# Clock_Schematic_v_7.net
KiCad netlist of a schematic drawn in EAGLE
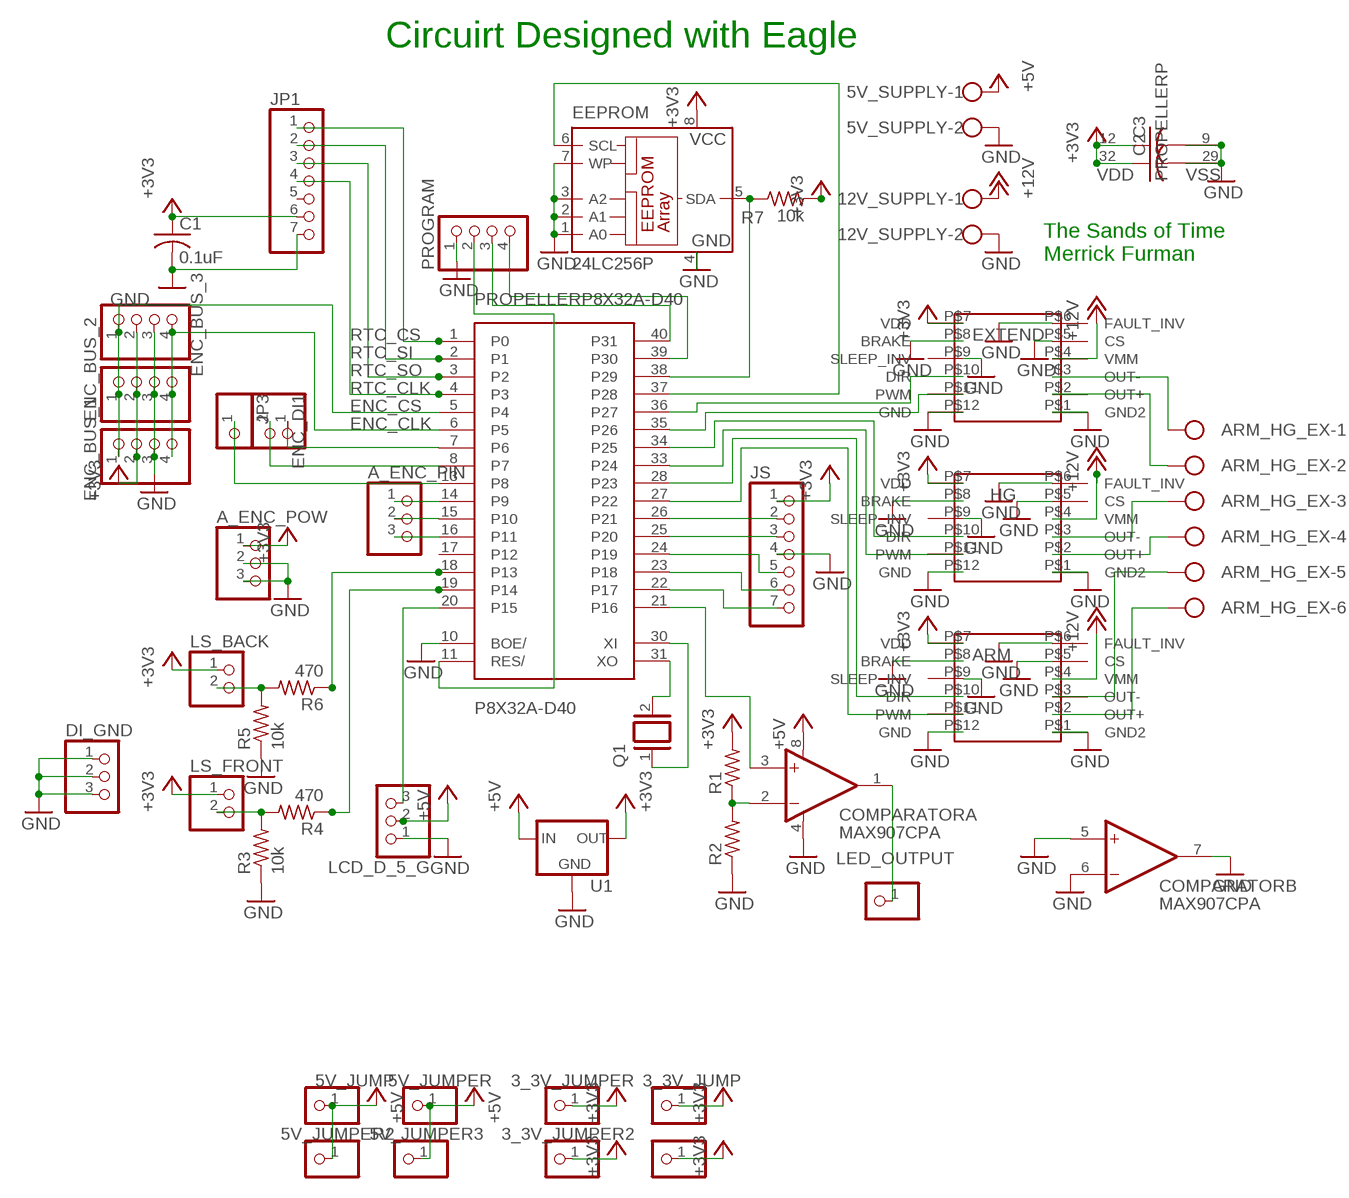
[diagram p0: schematic, sheet 1]

(export (version "E")
  (design (tool "Eeschema 10.0.6"))
  (components
    (comp (ref "3_3V_JUMP")
      (value "PINHD-1X1")
      (footprint "eagle-import:1X01")
      (libsource (lib "eagle-import") (part "PINHD-1X1"))
    )
    (comp (ref "3_3V_JUMPER")
      (value "PINHD-1X1")
      (footprint "eagle-import:1X01")
      (libsource (lib "eagle-import") (part "PINHD-1X1"))
    )
    (comp (ref "3_3V_JUMPER2")
      (value "PINHD-1X1")
      (footprint "eagle-import:1X01")
      (libsource (lib "eagle-import") (part "PINHD-1X1"))
    )
    (comp (ref "3_3V_JUMPER3")
      (value "PINHD-1X1")
      (footprint "eagle-import:1X01")
      (libsource (lib "eagle-import") (part "PINHD-1X1"))
    )
    (comp (ref "5V_JUMP")
      (value "PINHD-1X1")
      (footprint "eagle-import:1X01")
      (libsource (lib "eagle-import") (part "PINHD-1X1"))
    )
    (comp (ref "5V_JUMPER")
      (value "PINHD-1X1")
      (footprint "eagle-import:1X01")
      (libsource (lib "eagle-import") (part "PINHD-1X1"))
    )
    (comp (ref "5V_JUMPER2")
      (value "PINHD-1X1")
      (footprint "eagle-import:1X01")
      (libsource (lib "eagle-import") (part "PINHD-1X1"))
    )
    (comp (ref "5V_JUMPER3")
      (value "PINHD-1X1")
      (footprint "eagle-import:1X01")
      (libsource (lib "eagle-import") (part "PINHD-1X1"))
    )
    (comp (ref "5V_SUPPLY")
      (value "W237-102")
      (footprint "eagle-import:W237-102")
      (fields (field (name "MPN") "237-102"))
      (libsource (lib "eagle-import") (part "W237-102"))
    )
    (comp (ref "12V_SUPPLY")
      (value "W237-102")
      (footprint "eagle-import:W237-102")
      (fields (field (name "MPN") "237-102"))
      (libsource (lib "eagle-import") (part "W237-102"))
    )
    (comp (ref "ARM")
      (value "DRV")
      (footprint "eagle-import:DRV")
      (libsource (lib "eagle-import") (part "DRV"))
    )
    (comp (ref "ARM_HG_EX")
      (value "W237-6")
      (footprint "eagle-import:W237-6")
      (libsource (lib "eagle-import") (part "W237-6"))
    )
    (comp (ref "A_ENC_PIN")
      (value "PINHD-1X3")
      (footprint "eagle-import:1X03")
      (libsource (lib "eagle-import") (part "PINHD-1X3"))
    )
    (comp (ref "A_ENC_POW")
      (value "PINHD-1X3")
      (footprint "eagle-import:1X03")
      (libsource (lib "eagle-import") (part "PINHD-1X3"))
    )
    (comp (ref "C1")
      (value "0.1uF")
      (footprint "eagle-import:C050-025X075")
      (libsource (lib "eagle-import") (part "C-US050-025X075"))
    )
    (comp (ref "C2")
      (value "C-US050-025X075")
      (footprint "eagle-import:C050-025X075")
      (libsource (lib "eagle-import") (part "C-US050-025X075"))
    )
    (comp (ref "C3")
      (value "C-US050-025X075")
      (footprint "eagle-import:C050-025X075")
      (libsource (lib "eagle-import") (part "C-US050-025X075"))
    )
    (comp (ref "COMPARATOR")
      (value "MAX907CPA")
      (footprint "eagle-import:DIL08")
      (fields (field (name "MF") "MAXIM") (field (name "SPICEPREFIX") "X"))
      (libsource (lib "eagle-import") (part "MAX907CPA"))
    )
    (comp (ref "DI_GND")
      (value "PINHD-1X3")
      (footprint "eagle-import:1X03")
      (libsource (lib "eagle-import") (part "PINHD-1X3"))
    )
    (comp (ref "EEPROM")
      (value "24LC256P")
      (footprint "eagle-import:DIL8")
      (fields (field (name "MF") "MICROCHIP") (field (name "MPN") "24LC256-E/P"))
      (libsource (lib "eagle-import") (part "24PLC256"))
    )
    (comp (ref "ENC_BUS_1")
      (value "PINHD-1X4")
      (footprint "eagle-import:1X04")
      (libsource (lib "eagle-import") (part "PINHD-1X4"))
    )
    (comp (ref "ENC_BUS_2")
      (value "PINHD-1X4")
      (footprint "eagle-import:1X04")
      (libsource (lib "eagle-import") (part "PINHD-1X4"))
    )
    (comp (ref "ENC_BUS_3")
      (value "PINHD-1X4")
      (footprint "eagle-import:1X04")
      (libsource (lib "eagle-import") (part "PINHD-1X4"))
    )
    (comp (ref "ENC_DI1")
      (value "PINHD-1X2")
      (footprint "eagle-import:1X02")
      (libsource (lib "eagle-import") (part "PINHD-1X2"))
    )
    (comp (ref "EXTEND")
      (value "DRV")
      (footprint "eagle-import:DRV")
      (libsource (lib "eagle-import") (part "DRV"))
    )
    (comp (ref "HG")
      (value "DRV")
      (footprint "eagle-import:DRV")
      (libsource (lib "eagle-import") (part "DRV"))
    )
    (comp (ref "JP1")
      (value "PINHD-1X7")
      (footprint "eagle-import:1X07")
      (libsource (lib "eagle-import") (part "PINHD-1X7"))
    )
    (comp (ref "JP3")
      (value "PINHD-1X1")
      (footprint "eagle-import:1X01")
      (libsource (lib "eagle-import") (part "PINHD-1X1"))
    )
    (comp (ref "JS")
      (value "PINHD-1X7")
      (footprint "eagle-import:1X07")
      (libsource (lib "eagle-import") (part "PINHD-1X7"))
    )
    (comp (ref "LCD_D_5_G")
      (value "PINHD-1X3")
      (footprint "eagle-import:1X03")
      (libsource (lib "eagle-import") (part "PINHD-1X3"))
    )
    (comp (ref "LED_OUTPUT")
      (value "PINHD-1X1")
      (footprint "eagle-import:1X01")
      (libsource (lib "eagle-import") (part "PINHD-1X1"))
    )
    (comp (ref "LS_BACK")
      (value "PINHD-1X2")
      (footprint "eagle-import:1X02")
      (libsource (lib "eagle-import") (part "PINHD-1X2"))
    )
    (comp (ref "LS_FRONT")
      (value "PINHD-1X2")
      (footprint "eagle-import:1X02")
      (libsource (lib "eagle-import") (part "PINHD-1X2"))
    )
    (comp (ref "PROGRAM")
      (value "PINHD-1X4")
      (footprint "eagle-import:1X04")
      (libsource (lib "eagle-import") (part "PINHD-1X4"))
    )
    (comp (ref "PROPELLER")
      (value "P8X32A-D40")
      (footprint "eagle-import:P8X32A-D40")
      (libsource (lib "eagle-import") (part "P8X32A-D40"))
    )
    (comp (ref "Q1")
      (value "XTAL/S")
      (footprint "eagle-import:QS")
      (libsource (lib "eagle-import") (part "XTAL/S"))
    )
    (comp (ref "R1")
      (value "R-US_0207/10")
      (footprint "eagle-import:0207_10")
      (libsource (lib "eagle-import") (part "R-US_0207/10"))
    )
    (comp (ref "R2")
      (value "R-US_0207/10")
      (footprint "eagle-import:0207_10")
      (libsource (lib "eagle-import") (part "R-US_0207/10"))
    )
    (comp (ref "R3")
      (value "10k")
      (footprint "eagle-import:0207_10")
      (libsource (lib "eagle-import") (part "R-US_0207/10"))
    )
    (comp (ref "R4")
      (value "470")
      (footprint "eagle-import:0207_10")
      (libsource (lib "eagle-import") (part "R-US_0207/10"))
    )
    (comp (ref "R5")
      (value "10k")
      (footprint "eagle-import:0207_10")
      (libsource (lib "eagle-import") (part "R-US_0207/10"))
    )
    (comp (ref "R6")
      (value "470")
      (footprint "eagle-import:0207_10")
      (libsource (lib "eagle-import") (part "R-US_0207/10"))
    )
    (comp (ref "R7")
      (value "10k")
      (footprint "eagle-import:0207_10")
      (libsource (lib "eagle-import") (part "R-US_0207/10"))
    )
    (comp (ref "U1")
      (value "V_REG_78XXSIDE")
      (footprint "eagle-import:78XXL")
      (libsource (lib "eagle-import") (part "V_REG_78XXSIDE"))
    )
  )
  (nets
    (net (code "1") (name "+3V3") (class "Default")
      (node (ref "3_3V_JUMP") (pin "1") (pinfunction "1_1") (pintype "passive"))
      (node (ref "3_3V_JUMPER") (pin "1") (pinfunction "1_1") (pintype "passive"))
      (node (ref "3_3V_JUMPER2") (pin "1") (pinfunction "1_1") (pintype "passive"))
      (node (ref "3_3V_JUMPER3") (pin "1") (pinfunction "1_1") (pintype "passive"))
      (node (ref "ARM") (pin "P$7") (pinfunction "VDD_P$7") (pintype "bidirectional"))
      (node (ref "A_ENC_POW") (pin "1") (pinfunction "1_1") (pintype "passive"))
      (node (ref "C1") (pin "1") (pinfunction "1_1") (pintype "passive"))
      (node (ref "C2") (pin "1") (pinfunction "1_1") (pintype "passive"))
      (node (ref "C3") (pin "1") (pinfunction "1_1") (pintype "passive"))
      (node (ref "EEPROM") (pin "8") (pinfunction "VCC_8") (pintype "power_in"))
      (node (ref "ENC_BUS_1") (pin "2") (pinfunction "2_2") (pintype "passive"))
      (node (ref "ENC_BUS_2") (pin "2") (pinfunction "2_2") (pintype "passive"))
      (node (ref "ENC_BUS_3") (pin "2") (pinfunction "2_2") (pintype "passive"))
      (node (ref "EXTEND") (pin "P$7") (pinfunction "VDD_P$7") (pintype "bidirectional"))
      (node (ref "HG") (pin "P$7") (pinfunction "VDD_P$7") (pintype "bidirectional"))
      (node (ref "JP1") (pin "6") (pinfunction "6_6") (pintype "passive"))
      (node (ref "JS") (pin "1") (pinfunction "1_1") (pintype "passive"))
      (node (ref "LS_BACK") (pin "1") (pinfunction "1_1") (pintype "passive"))
      (node (ref "LS_FRONT") (pin "1") (pinfunction "1_1") (pintype "passive"))
      (node (ref "PROPELLER") (pin "12") (pinfunction "VDD_12") (pintype "power_in"))
      (node (ref "PROPELLER") (pin "32") (pinfunction "VDD_32") (pintype "power_in"))
      (node (ref "R1") (pin "2") (pinfunction "2_2") (pintype "passive"))
      (node (ref "R7") (pin "2") (pinfunction "2_2") (pintype "passive"))
      (node (ref "U1") (pin "OUT") (pinfunction "OUT_OUT") (pintype "passive"))
    )
    (net (code "2") (name "+5V") (class "Default")
      (node (ref "5V_JUMP") (pin "1") (pinfunction "1_1") (pintype "passive"))
      (node (ref "5V_JUMPER") (pin "1") (pinfunction "1_1") (pintype "passive"))
      (node (ref "5V_JUMPER2") (pin "1") (pinfunction "1_1") (pintype "passive"))
      (node (ref "5V_JUMPER3") (pin "1") (pinfunction "1_1") (pintype "passive"))
      (node (ref "5V_SUPPLY") (pin "1") (pinfunction "KL_1") (pintype "passive"))
      (node (ref "COMPARATOR") (pin "8") (pinfunction "V+_8") (pintype "power_in"))
      (node (ref "LCD_D_5_G") (pin "2") (pinfunction "2_2") (pintype "passive"))
      (node (ref "U1") (pin "IN") (pinfunction "IN_IN") (pintype "input"))
    )
    (net (code "3") (name "+12V") (class "Default")
      (node (ref "12V_SUPPLY") (pin "1") (pinfunction "KL_1") (pintype "passive"))
      (node (ref "ARM") (pin "P$4") (pinfunction "VMM_P$4") (pintype "bidirectional"))
      (node (ref "EXTEND") (pin "P$4") (pinfunction "VMM_P$4") (pintype "bidirectional"))
      (node (ref "HG") (pin "P$4") (pinfunction "VMM_P$4") (pintype "bidirectional"))
    )
    (net (code "4") (name "/ENC_CLK") (class "Default")
      (node (ref "ENC_BUS_1") (pin "4") (pinfunction "4_4") (pintype "passive"))
      (node (ref "ENC_BUS_2") (pin "4") (pinfunction "4_4") (pintype "passive"))
      (node (ref "ENC_BUS_3") (pin "4") (pinfunction "4_4") (pintype "passive"))
      (node (ref "PROPELLER") (pin "6") (pinfunction "P5_6") (pintype "bidirectional"))
    )
    (net (code "5") (name "/ENC_CS") (class "Default")
      (node (ref "ENC_BUS_1") (pin "1") (pinfunction "1_1") (pintype "passive"))
      (node (ref "ENC_BUS_2") (pin "1") (pinfunction "1_1") (pintype "passive"))
      (node (ref "ENC_BUS_3") (pin "1") (pinfunction "1_1") (pintype "passive"))
      (node (ref "PROPELLER") (pin "5") (pinfunction "P4_5") (pintype "bidirectional"))
    )
    (net (code "6") (name "/RTC_CLK") (class "Default")
      (node (ref "JP1") (pin "4") (pinfunction "4_4") (pintype "passive"))
      (node (ref "PROPELLER") (pin "4") (pinfunction "P3_4") (pintype "bidirectional"))
    )
    (net (code "7") (name "/RTC_CS") (class "Default")
      (node (ref "JP1") (pin "1") (pinfunction "1_1") (pintype "passive"))
      (node (ref "PROPELLER") (pin "1") (pinfunction "P0_1") (pintype "bidirectional"))
    )
    (net (code "8") (name "/RTC_SI") (class "Default")
      (node (ref "JP1") (pin "2") (pinfunction "2_2") (pintype "passive"))
      (node (ref "PROPELLER") (pin "2") (pinfunction "P1_2") (pintype "bidirectional"))
    )
    (net (code "9") (name "/RTC_SO") (class "Default")
      (node (ref "JP1") (pin "3") (pinfunction "3_3") (pintype "passive"))
      (node (ref "PROPELLER") (pin "3") (pinfunction "P2_3") (pintype "bidirectional"))
    )
    (net (code "10") (name "GND") (class "Default")
      (node (ref "12V_SUPPLY") (pin "2") (pinfunction "KL_2") (pintype "passive"))
      (node (ref "5V_SUPPLY") (pin "2") (pinfunction "KL_2") (pintype "passive"))
      (node (ref "ARM") (pin "P$1") (pinfunction "GND2_P$1") (pintype "bidirectional"))
      (node (ref "ARM") (pin "P$12") (pinfunction "GND_P$12") (pintype "bidirectional"))
      (node (ref "ARM") (pin "P$5") (pinfunction "CS_P$5") (pintype "bidirectional"))
      (node (ref "ARM") (pin "P$6") (pinfunction "FAULT_INV_P$6") (pintype "bidirectional"))
      (node (ref "ARM") (pin "P$8") (pinfunction "BRAKE_P$8") (pintype "bidirectional"))
      (node (ref "ARM") (pin "P$9") (pinfunction "SLEEP_INV_P$9") (pintype "bidirectional"))
      (node (ref "A_ENC_POW") (pin "2") (pinfunction "2_2") (pintype "passive"))
      (node (ref "A_ENC_POW") (pin "3") (pinfunction "3_3") (pintype "passive"))
      (node (ref "C1") (pin "2") (pinfunction "2_2") (pintype "passive"))
      (node (ref "C2") (pin "2") (pinfunction "2_2") (pintype "passive"))
      (node (ref "C3") (pin "2") (pinfunction "2_2") (pintype "passive"))
      (node (ref "COMPARATOR") (pin "4") (pinfunction "V-_4") (pintype "power_in"))
      (node (ref "COMPARATOR") (pin "5") (pinfunction "+IN_5") (pintype "input"))
      (node (ref "COMPARATOR") (pin "6") (pinfunction "-IN_6") (pintype "input"))
      (node (ref "COMPARATOR") (pin "7") (pinfunction "OUT_7") (pintype "output"))
      (node (ref "DI_GND") (pin "1") (pinfunction "1_1") (pintype "passive"))
      (node (ref "DI_GND") (pin "2") (pinfunction "2_2") (pintype "passive"))
      (node (ref "DI_GND") (pin "3") (pinfunction "3_3") (pintype "passive"))
      (node (ref "EEPROM") (pin "1") (pinfunction "A0_1") (pintype "input"))
      (node (ref "EEPROM") (pin "2") (pinfunction "A1_2") (pintype "input"))
      (node (ref "EEPROM") (pin "3") (pinfunction "A2_3") (pintype "input"))
      (node (ref "EEPROM") (pin "4") (pinfunction "GND_4") (pintype "power_in"))
      (node (ref "EEPROM") (pin "7") (pinfunction "WP_7") (pintype "input"))
      (node (ref "ENC_BUS_1") (pin "3") (pinfunction "3_3") (pintype "passive"))
      (node (ref "ENC_BUS_2") (pin "3") (pinfunction "3_3") (pintype "passive"))
      (node (ref "ENC_BUS_3") (pin "3") (pinfunction "3_3") (pintype "passive"))
      (node (ref "EXTEND") (pin "P$1") (pinfunction "GND2_P$1") (pintype "bidirectional"))
      (node (ref "EXTEND") (pin "P$12") (pinfunction "GND_P$12") (pintype "bidirectional"))
      (node (ref "EXTEND") (pin "P$5") (pinfunction "CS_P$5") (pintype "bidirectional"))
      (node (ref "EXTEND") (pin "P$6") (pinfunction "FAULT_INV_P$6") (pintype "bidirectional"))
      (node (ref "EXTEND") (pin "P$8") (pinfunction "BRAKE_P$8") (pintype "bidirectional"))
      (node (ref "EXTEND") (pin "P$9") (pinfunction "SLEEP_INV_P$9") (pintype "bidirectional"))
      (node (ref "HG") (pin "P$1") (pinfunction "GND2_P$1") (pintype "bidirectional"))
      (node (ref "HG") (pin "P$12") (pinfunction "GND_P$12") (pintype "bidirectional"))
      (node (ref "HG") (pin "P$5") (pinfunction "CS_P$5") (pintype "bidirectional"))
      (node (ref "HG") (pin "P$6") (pinfunction "FAULT_INV_P$6") (pintype "bidirectional"))
      (node (ref "HG") (pin "P$8") (pinfunction "BRAKE_P$8") (pintype "bidirectional"))
      (node (ref "HG") (pin "P$9") (pinfunction "SLEEP_INV_P$9") (pintype "bidirectional"))
      (node (ref "JP1") (pin "7") (pinfunction "7_7") (pintype "passive"))
      (node (ref "JS") (pin "4") (pinfunction "4_4") (pintype "passive"))
      (node (ref "LCD_D_5_G") (pin "1") (pinfunction "1_1") (pintype "passive"))
      (node (ref "PROGRAM") (pin "1") (pinfunction "1_1") (pintype "passive"))
      (node (ref "PROPELLER") (pin "10") (pinfunction "BOE/_10") (pintype "input"))
      (node (ref "PROPELLER") (pin "29") (pinfunction "VSS_29") (pintype "power_in"))
      (node (ref "PROPELLER") (pin "9") (pinfunction "VSS_9") (pintype "power_in"))
      (node (ref "R2") (pin "1") (pinfunction "1_1") (pintype "passive"))
      (node (ref "R3") (pin "1") (pinfunction "1_1") (pintype "passive"))
      (node (ref "R5") (pin "1") (pinfunction "1_1") (pintype "passive"))
      (node (ref "U1") (pin "GND") (pinfunction "GND_GND") (pintype "input"))
    )
    (net (code "11") (name "Net-(ARM-DIR)") (class "Default")
      (node (ref "ARM") (pin "P$10") (pinfunction "DIR_P$10") (pintype "bidirectional"))
      (node (ref "PROPELLER") (pin "28") (pinfunction "P23_28") (pintype "bidirectional"))
    )
    (net (code "12") (name "Net-(ARM-OUT+)") (class "Default")
      (node (ref "ARM") (pin "P$2") (pinfunction "OUT+_P$2") (pintype "bidirectional"))
      (node (ref "ARM_HG_EX") (pin "6") (pinfunction "KL_6") (pintype "passive"))
    )
    (net (code "13") (name "Net-(ARM-OUT-)") (class "Default")
      (node (ref "ARM") (pin "P$3") (pinfunction "OUT-_P$3") (pintype "bidirectional"))
      (node (ref "ARM_HG_EX") (pin "5") (pinfunction "KL_5") (pintype "passive"))
    )
    (net (code "14") (name "Net-(ARM-PWM)") (class "Default")
      (node (ref "ARM") (pin "P$11") (pinfunction "PWM_P$11") (pintype "bidirectional"))
      (node (ref "PROPELLER") (pin "27") (pinfunction "P22_27") (pintype "bidirectional"))
    )
    (net (code "15") (name "Net-(ARM_HG_EXA-KL)") (class "Default")
      (node (ref "ARM_HG_EX") (pin "1") (pinfunction "KL_1") (pintype "passive"))
      (node (ref "EXTEND") (pin "P$3") (pinfunction "OUT-_P$3") (pintype "bidirectional"))
    )
    (net (code "16") (name "Net-(ARM_HG_EXB-KL)") (class "Default")
      (node (ref "ARM_HG_EX") (pin "2") (pinfunction "KL_2") (pintype "passive"))
      (node (ref "EXTEND") (pin "P$2") (pinfunction "OUT+_P$2") (pintype "bidirectional"))
    )
    (net (code "17") (name "Net-(ARM_HG_EXC-KL)") (class "Default")
      (node (ref "ARM_HG_EX") (pin "3") (pinfunction "KL_3") (pintype "passive"))
      (node (ref "HG") (pin "P$3") (pinfunction "OUT-_P$3") (pintype "bidirectional"))
    )
    (net (code "18") (name "Net-(ARM_HG_EXD-KL)") (class "Default")
      (node (ref "ARM_HG_EX") (pin "4") (pinfunction "KL_4") (pintype "passive"))
      (node (ref "HG") (pin "P$2") (pinfunction "OUT+_P$2") (pintype "bidirectional"))
    )
    (net (code "19") (name "Net-(COMPARATORA-+IN)") (class "Default")
      (node (ref "COMPARATOR") (pin "3") (pinfunction "+IN_3") (pintype "input"))
      (node (ref "PROPELLER") (pin "21") (pinfunction "P16_21") (pintype "bidirectional"))
    )
    (net (code "20") (name "Net-(COMPARATORA--IN)") (class "Default")
      (node (ref "COMPARATOR") (pin "2") (pinfunction "-IN_2") (pintype "input"))
      (node (ref "R1") (pin "1") (pinfunction "1_1") (pintype "passive"))
      (node (ref "R2") (pin "2") (pinfunction "2_2") (pintype "passive"))
    )
    (net (code "21") (name "Net-(COMPARATORA-OUT)") (class "Default")
      (node (ref "COMPARATOR") (pin "1") (pinfunction "OUT_1") (pintype "output"))
      (node (ref "LED_OUTPUT") (pin "1") (pinfunction "1_1") (pintype "passive"))
    )
    (net (code "22") (name "Net-(EEPROM-SCL)") (class "Default")
      (node (ref "EEPROM") (pin "6") (pinfunction "SCL_6") (pintype "input"))
      (node (ref "PROPELLER") (pin "37") (pinfunction "P28_37") (pintype "bidirectional"))
    )
    (net (code "23") (name "Net-(EEPROM-SDA)") (class "Default")
      (node (ref "EEPROM") (pin "5") (pinfunction "SDA_5") (pintype "bidirectional"))
      (node (ref "PROPELLER") (pin "38") (pinfunction "P29_38") (pintype "bidirectional"))
      (node (ref "R7") (pin "1") (pinfunction "1_1") (pintype "passive"))
    )
    (net (code "24") (name "Net-(EXTEND-DIR)") (class "Default")
      (node (ref "EXTEND") (pin "P$10") (pinfunction "DIR_P$10") (pintype "bidirectional"))
      (node (ref "PROPELLER") (pin "36") (pinfunction "P27_36") (pintype "bidirectional"))
    )
    (net (code "25") (name "Net-(EXTEND-PWM)") (class "Default")
      (node (ref "EXTEND") (pin "P$11") (pinfunction "PWM_P$11") (pintype "bidirectional"))
      (node (ref "PROPELLER") (pin "35") (pinfunction "P26_35") (pintype "bidirectional"))
    )
    (net (code "26") (name "Net-(HG-DIR)") (class "Default")
      (node (ref "HG") (pin "P$10") (pinfunction "DIR_P$10") (pintype "bidirectional"))
      (node (ref "PROPELLER") (pin "34") (pinfunction "P25_34") (pintype "bidirectional"))
    )
    (net (code "27") (name "Net-(HG-PWM)") (class "Default")
      (node (ref "HG") (pin "P$11") (pinfunction "PWM_P$11") (pintype "bidirectional"))
      (node (ref "PROPELLER") (pin "33") (pinfunction "P24_33") (pintype "bidirectional"))
    )
    (net (code "28") (name "Net-(LS_BACK-Pad2)") (class "Default")
      (node (ref "LS_BACK") (pin "2") (pinfunction "2_2") (pintype "passive"))
      (node (ref "R5") (pin "2") (pinfunction "2_2") (pintype "passive"))
      (node (ref "R6") (pin "2") (pinfunction "2_2") (pintype "passive"))
    )
    (net (code "29") (name "Net-(LS_FRONT-Pad2)") (class "Default")
      (node (ref "LS_FRONT") (pin "2") (pinfunction "2_2") (pintype "passive"))
      (node (ref "R3") (pin "2") (pinfunction "2_2") (pintype "passive"))
      (node (ref "R4") (pin "2") (pinfunction "2_2") (pintype "passive"))
    )
    (net (code "30") (name "Net-(PROPELLERB-P6)") (class "Default")
      (node (ref "ENC_DI1") (pin "1") (pinfunction "1_1") (pintype "passive"))
      (node (ref "PROPELLER") (pin "7") (pinfunction "P6_7") (pintype "bidirectional"))
    )
    (net (code "31") (name "Net-(PROPELLERB-P7)") (class "Default")
      (node (ref "ENC_DI1") (pin "2") (pinfunction "2_2") (pintype "passive"))
      (node (ref "PROPELLER") (pin "8") (pinfunction "P7_8") (pintype "bidirectional"))
    )
    (net (code "32") (name "Net-(PROPELLERB-P8)") (class "Default")
      (node (ref "JP3") (pin "1") (pinfunction "1_1") (pintype "passive"))
      (node (ref "PROPELLER") (pin "13") (pinfunction "P8_13") (pintype "bidirectional"))
    )
    (net (code "33") (name "Net-(PROPELLERB-P9)") (class "Default")
      (node (ref "A_ENC_PIN") (pin "1") (pinfunction "1_1") (pintype "passive"))
      (node (ref "PROPELLER") (pin "14") (pinfunction "P9_14") (pintype "bidirectional"))
    )
    (net (code "34") (name "Net-(PROPELLERB-P10)") (class "Default")
      (node (ref "A_ENC_PIN") (pin "2") (pinfunction "2_2") (pintype "passive"))
      (node (ref "PROPELLER") (pin "15") (pinfunction "P10_15") (pintype "bidirectional"))
    )
    (net (code "35") (name "Net-(PROPELLERB-P11)") (class "Default")
      (node (ref "A_ENC_PIN") (pin "3") (pinfunction "3_3") (pintype "passive"))
      (node (ref "PROPELLER") (pin "16") (pinfunction "P11_16") (pintype "bidirectional"))
    )
    (net (code "36") (name "Net-(PROPELLERB-P13)") (class "Default")
      (node (ref "PROPELLER") (pin "18") (pinfunction "P13_18") (pintype "bidirectional"))
      (node (ref "R6") (pin "1") (pinfunction "1_1") (pintype "passive"))
    )
    (net (code "37") (name "Net-(PROPELLERB-P14)") (class "Default")
      (node (ref "PROPELLER") (pin "19") (pinfunction "P14_19") (pintype "bidirectional"))
      (node (ref "R4") (pin "1") (pinfunction "1_1") (pintype "passive"))
    )
    (net (code "38") (name "Net-(PROPELLERB-P15)") (class "Default")
      (node (ref "LCD_D_5_G") (pin "3") (pinfunction "3_3") (pintype "passive"))
      (node (ref "PROPELLER") (pin "20") (pinfunction "P15_20") (pintype "bidirectional"))
    )
    (net (code "39") (name "Net-(PROPELLERB-P17)") (class "Default")
      (node (ref "JS") (pin "7") (pinfunction "7_7") (pintype "passive"))
      (node (ref "PROPELLER") (pin "22") (pinfunction "P17_22") (pintype "bidirectional"))
    )
    (net (code "40") (name "Net-(PROPELLERB-P18)") (class "Default")
      (node (ref "JS") (pin "6") (pinfunction "6_6") (pintype "passive"))
      (node (ref "PROPELLER") (pin "23") (pinfunction "P18_23") (pintype "bidirectional"))
    )
    (net (code "41") (name "Net-(PROPELLERB-P19)") (class "Default")
      (node (ref "JS") (pin "5") (pinfunction "5_5") (pintype "passive"))
      (node (ref "PROPELLER") (pin "24") (pinfunction "P19_24") (pintype "bidirectional"))
    )
    (net (code "42") (name "Net-(PROPELLERB-P20)") (class "Default")
      (node (ref "JS") (pin "3") (pinfunction "3_3") (pintype "passive"))
      (node (ref "PROPELLER") (pin "25") (pinfunction "P20_25") (pintype "bidirectional"))
    )
    (net (code "43") (name "Net-(PROPELLERB-P21)") (class "Default")
      (node (ref "JS") (pin "2") (pinfunction "2_2") (pintype "passive"))
      (node (ref "PROPELLER") (pin "26") (pinfunction "P21_26") (pintype "bidirectional"))
    )
    (net (code "44") (name "Net-(PROPELLERB-P30)") (class "Default")
      (node (ref "PROGRAM") (pin "4") (pinfunction "4_4") (pintype "passive"))
      (node (ref "PROPELLER") (pin "39") (pinfunction "P30_39") (pintype "bidirectional"))
    )
    (net (code "45") (name "Net-(PROPELLERB-P31)") (class "Default")
      (node (ref "PROGRAM") (pin "3") (pinfunction "3_3") (pintype "passive"))
      (node (ref "PROPELLER") (pin "40") (pinfunction "P31_40") (pintype "bidirectional"))
    )
    (net (code "46") (name "Net-(PROPELLERB-RES{slash})") (class "Default")
      (node (ref "PROGRAM") (pin "2") (pinfunction "2_2") (pintype "passive"))
      (node (ref "PROPELLER") (pin "11") (pinfunction "RES/_11") (pintype "bidirectional"))
    )
    (net (code "47") (name "Net-(PROPELLERB-XI)") (class "Default")
      (node (ref "PROPELLER") (pin "30") (pinfunction "XI_30") (pintype "input"))
      (node (ref "Q1") (pin "1") (pinfunction "1_1") (pintype "passive"))
    )
    (net (code "48") (name "Net-(PROPELLERB-XO)") (class "Default")
      (node (ref "PROPELLER") (pin "31") (pinfunction "XO_31") (pintype "output"))
      (node (ref "Q1") (pin "2") (pinfunction "2_2") (pintype "passive"))
    )
    (net (code "49") (name "unconnected-(JP1-Pad5)") (class "Default")
      (node (ref "JP1") (pin "5") (pinfunction "5_5") (pintype "passive"))
    )
    (net (code "50") (name "unconnected-(PROPELLERB-P12-Pad17)") (class "Default")
      (node (ref "PROPELLER") (pin "17") (pinfunction "P12_17") (pintype "bidirectional"))
    )
  )
)
